# Qwiic_RFID_-_IDXXLA.net
KiCad netlist of a schematic drawn in EAGLE
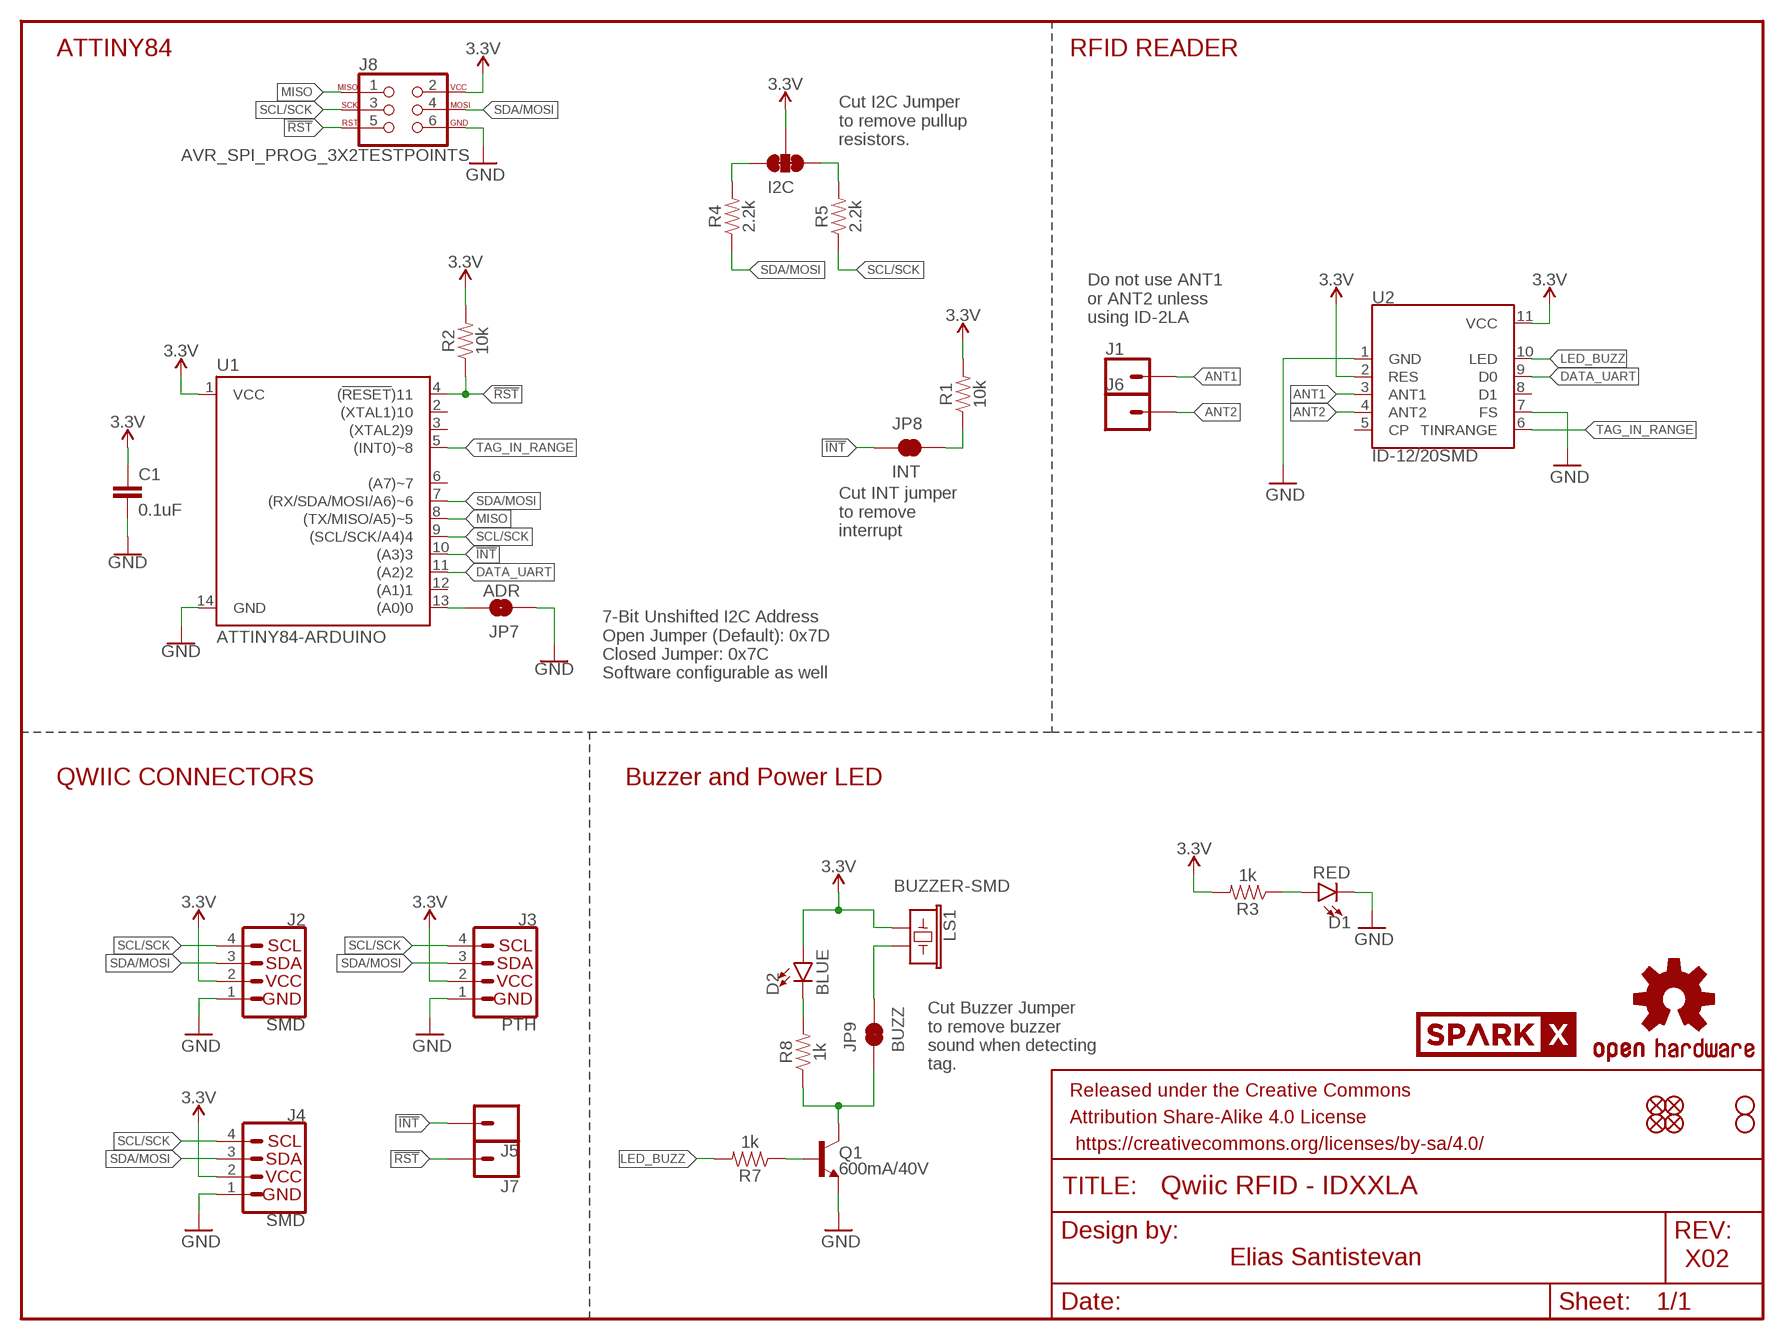
[diagram p0: schematic, sheet 1]

(export (version "E")
  (design (tool "Eeschema 10.0.6"))
  (components
    (comp (ref "C1")
      (value "0.1uF")
      (footprint "eagle-import:0603")
      (libsource (lib "eagle-import") (part "0.1UF-0603-25V-(+80/-20%)"))
    )
    (comp (ref "D1")
      (value "RED")
      (footprint "eagle-import:LED-0603")
      (libsource (lib "eagle-import") (part "LED-RED0603"))
    )
    (comp (ref "D2")
      (value "BLUE")
      (footprint "eagle-import:LED-0603")
      (libsource (lib "eagle-import") (part "LED-BLUE0603"))
    )
    (comp (ref "FRAME1")
      (value "FRAME-LETTER")
      (footprint "eagle-import:CREATIVE_COMMONS")
      (libsource (lib "eagle-import") (part "FRAME-LETTER"))
    )
    (comp (ref "I2C")
      (value "JUMPER-SMT_3_2-NC_TRACE_SILK")
      (footprint "eagle-import:SMT-JUMPER_3_2-NC_TRACE_SILK")
      (libsource (lib "eagle-import") (part "JUMPER-SMT_3_2-NC_TRACE_SILK"))
    )
    (comp (ref "J1")
      (value "CONN_01PTH_NO_SILK_YES_STOP")
      (footprint "eagle-import:1X01_NO_SILK")
      (libsource (lib "eagle-import") (part "CONN_01PTH_NO_SILK_YES_STOP"))
    )
    (comp (ref "J2")
      (value "SMD")
      (footprint "eagle-import:1X04_1MM_RA")
      (libsource (lib "eagle-import") (part "I2C_STANDARDJS-1MM"))
    )
    (comp (ref "J3")
      (value "PTH")
      (footprint "eagle-import:1X04_NO_SILK")
      (libsource (lib "eagle-import") (part "I2C_STANDARD_NO_SILK"))
    )
    (comp (ref "J4")
      (value "SMD")
      (footprint "eagle-import:1X04_1MM_RA")
      (libsource (lib "eagle-import") (part "I2C_STANDARDJS-1MM"))
    )
    (comp (ref "J5")
      (value "CONN_01PTH_NO_SILK_YES_STOP")
      (footprint "eagle-import:1X01_NO_SILK")
      (libsource (lib "eagle-import") (part "CONN_01PTH_NO_SILK_YES_STOP"))
    )
    (comp (ref "J6")
      (value "CONN_01PTH_NO_SILK_YES_STOP")
      (footprint "eagle-import:1X01_NO_SILK")
      (libsource (lib "eagle-import") (part "CONN_01PTH_NO_SILK_YES_STOP"))
    )
    (comp (ref "J7")
      (value "CONN_01PTH_NO_SILK_YES_STOP")
      (footprint "eagle-import:1X01_NO_SILK")
      (libsource (lib "eagle-import") (part "CONN_01PTH_NO_SILK_YES_STOP"))
    )
    (comp (ref "J8")
      (value "AVR_SPI_PROG_3X2TESTPOINTS")
      (footprint "eagle-import:2X3_TEST_POINTS")
      (libsource (lib "eagle-import") (part "AVR_SPI_PROG_3X2TESTPOINTS"))
    )
    (comp (ref "JP1")
      (value "FIDUCIALUFIDUCIAL")
      (footprint "eagle-import:MICRO-FIDUCIAL")
      (libsource (lib "eagle-import") (part "FIDUCIALUFIDUCIAL"))
    )
    (comp (ref "JP2")
      (value "FIDUCIALUFIDUCIAL")
      (footprint "eagle-import:MICRO-FIDUCIAL")
      (libsource (lib "eagle-import") (part "FIDUCIALUFIDUCIAL"))
    )
    (comp (ref "JP3")
      (value "STAND-OFF")
      (footprint "eagle-import:STAND-OFF")
      (libsource (lib "eagle-import") (part "STAND-OFF"))
    )
    (comp (ref "JP4")
      (value "STAND-OFF")
      (footprint "eagle-import:STAND-OFF")
      (libsource (lib "eagle-import") (part "STAND-OFF"))
    )
    (comp (ref "JP5")
      (value "FIDUCIALUFIDUCIAL")
      (footprint "eagle-import:MICRO-FIDUCIAL")
      (libsource (lib "eagle-import") (part "FIDUCIALUFIDUCIAL"))
    )
    (comp (ref "JP6")
      (value "FIDUCIALUFIDUCIAL")
      (footprint "eagle-import:MICRO-FIDUCIAL")
      (libsource (lib "eagle-import") (part "FIDUCIALUFIDUCIAL"))
    )
    (comp (ref "JP7")
      (value "ADR")
      (footprint "eagle-import:SMT-JUMPER_2_NO_SILK")
      (libsource (lib "eagle-import") (part "JUMPER-SMT_2_NO_SILK"))
    )
    (comp (ref "JP8")
      (value "INT")
      (footprint "eagle-import:SMT-JUMPER_2_NC_TRACE_SILK")
      (libsource (lib "eagle-import") (part "JUMPER-SMT_2_NC_TRACE_SILK"))
    )
    (comp (ref "JP9")
      (value "BUZZ")
      (footprint "eagle-import:SMT-JUMPER_2_NC_TRACE_SILK")
      (libsource (lib "eagle-import") (part "JUMPER-SMT_2_NC_TRACE_SILK"))
    )
    (comp (ref "LOGO1")
      (value "OSHW-LOGOMINI")
      (footprint "eagle-import:OSHW-LOGO-MINI")
      (libsource (lib "eagle-import") (part "OSHW-LOGOMINI"))
    )
    (comp (ref "LS1")
      (value "BUZZER-SMD")
      (footprint "eagle-import:BUZZER-CCV")
      (libsource (lib "eagle-import") (part "BUZZER-SMD"))
    )
    (comp (ref "Q1")
      (value "600mA/40V")
      (footprint "eagle-import:SOT23-3")
      (libsource (lib "eagle-import") (part "TRANS_NPN-MMBT2222AL"))
    )
    (comp (ref "R1")
      (value "10k")
      (footprint "eagle-import:0603")
      (libsource (lib "eagle-import") (part "10KOHM-0603-1/10W-1%"))
    )
    (comp (ref "R2")
      (value "10k")
      (footprint "eagle-import:0603")
      (libsource (lib "eagle-import") (part "10KOHM-0603-1/10W-1%"))
    )
    (comp (ref "R3")
      (value "1k")
      (footprint "eagle-import:0603")
      (libsource (lib "eagle-import") (part "1KOHM-0603-1/10W-1%"))
    )
    (comp (ref "R4")
      (value "2.2k")
      (footprint "eagle-import:0603")
      (libsource (lib "eagle-import") (part "2.2KOHM-0603-1/10W-1%"))
    )
    (comp (ref "R5")
      (value "2.2k")
      (footprint "eagle-import:0603")
      (libsource (lib "eagle-import") (part "2.2KOHM-0603-1/10W-1%"))
    )
    (comp (ref "R7")
      (value "1k")
      (footprint "eagle-import:0603")
      (libsource (lib "eagle-import") (part "1KOHM-0603-1/10W-1%"))
    )
    (comp (ref "R8")
      (value "1k")
      (footprint "eagle-import:0603")
      (libsource (lib "eagle-import") (part "1KOHM-0603-1/10W-1%"))
    )
    (comp (ref "U$4")
      (value "SPARKX-LOGO3")
      (footprint "eagle-import:SPARKX-SMALL")
      (libsource (lib "eagle-import") (part "SPARKX-LOGO3"))
    )
    (comp (ref "U1")
      (value "ATTINY84-ARDUINO")
      (footprint "eagle-import:SO14")
      (libsource (lib "eagle-import") (part "ATTINY84-ARDUINO"))
    )
    (comp (ref "U2")
      (value "ID-12/20SMD")
      (footprint "eagle-import:ID-12_SMD")
      (libsource (lib "eagle-import") (part "ID-12/20SMD"))
    )
  )
  (nets
    (net (code "1") (name "/~{INT}") (class "Default")
      (node (ref "J5") (pin "1") (pinfunction "1_1") (pintype "passive"))
      (node (ref "JP8") (pin "1") (pinfunction "1_1") (pintype "passive"))
      (node (ref "U1") (pin "10") (pinfunction "(A3)3_10") (pintype "bidirectional"))
    )
    (net (code "2") (name "/~{RST}") (class "Default")
      (node (ref "J7") (pin "1") (pinfunction "1_1") (pintype "passive"))
      (node (ref "J8") (pin "5") (pinfunction "5_5") (pintype "passive"))
      (node (ref "R2") (pin "1") (pinfunction "1_1") (pintype "passive"))
      (node (ref "U1") (pin "4") (pinfunction "(~{RESET})11_4") (pintype "bidirectional"))
    )
    (net (code "3") (name "3.3V") (class "Default")
      (node (ref "C1") (pin "1") (pinfunction "1_1") (pintype "passive"))
      (node (ref "D2") (pin "A") (pinfunction "A_A") (pintype "passive"))
      (node (ref "I2C") (pin "2") (pinfunction "2_2") (pintype "passive"))
      (node (ref "J2") (pin "2") (pinfunction "VCC_2") (pintype "power_in"))
      (node (ref "J3") (pin "2") (pinfunction "VCC_2") (pintype "power_in"))
      (node (ref "J4") (pin "2") (pinfunction "VCC_2") (pintype "power_in"))
      (node (ref "J8") (pin "2") (pinfunction "2_2") (pintype "passive"))
      (node (ref "LS1") (pin "+") (pinfunction "1_+") (pintype "passive"))
      (node (ref "R1") (pin "2") (pinfunction "2_2") (pintype "passive"))
      (node (ref "R2") (pin "2") (pinfunction "2_2") (pintype "passive"))
      (node (ref "R3") (pin "2") (pinfunction "2_2") (pintype "passive"))
      (node (ref "U1") (pin "1") (pinfunction "VCC_1") (pintype "bidirectional"))
      (node (ref "U2") (pin "11") (pinfunction "VCC_11") (pintype "bidirectional"))
      (node (ref "U2") (pin "2") (pinfunction "RES_2") (pintype "bidirectional"))
    )
    (net (code "4") (name "ANT1") (class "Default")
      (node (ref "J1") (pin "1") (pinfunction "1_1") (pintype "passive"))
      (node (ref "U2") (pin "3") (pinfunction "ANT1_3") (pintype "bidirectional"))
    )
    (net (code "5") (name "ANT2") (class "Default")
      (node (ref "J6") (pin "1") (pinfunction "1_1") (pintype "passive"))
      (node (ref "U2") (pin "4") (pinfunction "ANT2_4") (pintype "bidirectional"))
    )
    (net (code "6") (name "DATA_UART") (class "Default")
      (node (ref "U1") (pin "11") (pinfunction "(A2)2_11") (pintype "bidirectional"))
      (node (ref "U2") (pin "9") (pinfunction "D0_9") (pintype "bidirectional"))
    )
    (net (code "7") (name "GND") (class "Default")
      (node (ref "C1") (pin "2") (pinfunction "2_2") (pintype "passive"))
      (node (ref "D1") (pin "C") (pinfunction "C_C") (pintype "passive"))
      (node (ref "J2") (pin "1") (pinfunction "GND_1") (pintype "power_in"))
      (node (ref "J3") (pin "1") (pinfunction "GND_1") (pintype "power_in"))
      (node (ref "J4") (pin "1") (pinfunction "GND_1") (pintype "power_in"))
      (node (ref "J8") (pin "6") (pinfunction "6_6") (pintype "passive"))
      (node (ref "JP7") (pin "1") (pinfunction "1_1") (pintype "passive"))
      (node (ref "Q1") (pin "2") (pinfunction "E_2") (pintype "passive"))
      (node (ref "U1") (pin "14") (pinfunction "GND_14") (pintype "bidirectional"))
      (node (ref "U2") (pin "1") (pinfunction "GND_1") (pintype "bidirectional"))
      (node (ref "U2") (pin "7") (pinfunction "FS_7") (pintype "bidirectional"))
    )
    (net (code "8") (name "LED_BUZZ") (class "Default")
      (node (ref "R7") (pin "2") (pinfunction "2_2") (pintype "passive"))
      (node (ref "U2") (pin "10") (pinfunction "LED_10") (pintype "bidirectional"))
    )
    (net (code "9") (name "MISO") (class "Default")
      (node (ref "J8") (pin "1") (pinfunction "1_1") (pintype "passive"))
      (node (ref "U1") (pin "8") (pinfunction "(TX/MISO/A5)~{5}_8") (pintype "bidirectional"))
    )
    (net (code "10") (name "Net-(D1-PadA)") (class "Default")
      (node (ref "D1") (pin "A") (pinfunction "A_A") (pintype "passive"))
      (node (ref "R3") (pin "1") (pinfunction "1_1") (pintype "passive"))
    )
    (net (code "11") (name "Net-(D2-PadC)") (class "Default")
      (node (ref "D2") (pin "C") (pinfunction "C_C") (pintype "passive"))
      (node (ref "R8") (pin "2") (pinfunction "2_2") (pintype "passive"))
    )
    (net (code "12") (name "Net-(I2C-Pad1)") (class "Default")
      (node (ref "I2C") (pin "1") (pinfunction "1_1") (pintype "passive"))
      (node (ref "R5") (pin "2") (pinfunction "2_2") (pintype "passive"))
    )
    (net (code "13") (name "Net-(I2C-Pad3)") (class "Default")
      (node (ref "I2C") (pin "3") (pinfunction "3_3") (pintype "passive"))
      (node (ref "R4") (pin "2") (pinfunction "2_2") (pintype "passive"))
    )
    (net (code "14") (name "Net-(JP8-Pad2)") (class "Default")
      (node (ref "JP8") (pin "2") (pinfunction "2_2") (pintype "passive"))
      (node (ref "R1") (pin "1") (pinfunction "1_1") (pintype "passive"))
    )
    (net (code "15") (name "Net-(LS1-2)") (class "Default")
      (node (ref "JP9") (pin "2") (pinfunction "2_2") (pintype "passive"))
      (node (ref "LS1") (pin "-") (pinfunction "2_-") (pintype "passive"))
    )
    (net (code "16") (name "Net-(Q1-B)") (class "Default")
      (node (ref "Q1") (pin "1") (pinfunction "B_1") (pintype "passive"))
      (node (ref "R7") (pin "1") (pinfunction "1_1") (pintype "passive"))
    )
    (net (code "17") (name "Net-(Q1-C)") (class "Default")
      (node (ref "JP9") (pin "1") (pinfunction "1_1") (pintype "passive"))
      (node (ref "Q1") (pin "3") (pinfunction "C_3") (pintype "passive"))
      (node (ref "R8") (pin "1") (pinfunction "1_1") (pintype "passive"))
    )
    (net (code "18") (name "Net-(U1-(A0)0)") (class "Default")
      (node (ref "JP7") (pin "2") (pinfunction "2_2") (pintype "passive"))
      (node (ref "U1") (pin "13") (pinfunction "(A0)0_13") (pintype "bidirectional"))
    )
    (net (code "19") (name "SCL{slash}SCK") (class "Default")
      (node (ref "J2") (pin "4") (pinfunction "SCL_4") (pintype "passive"))
      (node (ref "J3") (pin "4") (pinfunction "SCL_4") (pintype "passive"))
      (node (ref "J4") (pin "4") (pinfunction "SCL_4") (pintype "passive"))
      (node (ref "J8") (pin "3") (pinfunction "3_3") (pintype "passive"))
      (node (ref "R5") (pin "1") (pinfunction "1_1") (pintype "passive"))
      (node (ref "U1") (pin "9") (pinfunction "(SCL/SCK/A4)4_9") (pintype "bidirectional"))
    )
    (net (code "20") (name "SDA{slash}MOSI") (class "Default")
      (node (ref "J2") (pin "3") (pinfunction "SDA_3") (pintype "passive"))
      (node (ref "J3") (pin "3") (pinfunction "SDA_3") (pintype "passive"))
      (node (ref "J4") (pin "3") (pinfunction "SDA_3") (pintype "passive"))
      (node (ref "J8") (pin "4") (pinfunction "4_4") (pintype "passive"))
      (node (ref "R4") (pin "1") (pinfunction "1_1") (pintype "passive"))
      (node (ref "U1") (pin "7") (pinfunction "(RX/SDA/MOSI/A6)~{6}_7") (pintype "bidirectional"))
    )
    (net (code "21") (name "TAG_IN_RANGE") (class "Default")
      (node (ref "U1") (pin "5") (pinfunction "(INT0)~{8}_5") (pintype "bidirectional"))
      (node (ref "U2") (pin "6") (pinfunction "TINRANGE_6") (pintype "bidirectional"))
    )
    (net (code "22") (name "unconnected-(U1-(A1)1-Pad12)") (class "Default")
      (node (ref "U1") (pin "12") (pinfunction "(A1)1_12") (pintype "bidirectional"))
    )
    (net (code "23") (name "unconnected-(U1-(A7)~{7}-Pad6)") (class "Default")
      (node (ref "U1") (pin "6") (pinfunction "(A7)~{7}_6") (pintype "bidirectional"))
    )
    (net (code "24") (name "unconnected-(U1-(XTAL1)10-Pad2)") (class "Default")
      (node (ref "U1") (pin "2") (pinfunction "(XTAL1)10_2") (pintype "bidirectional"))
    )
    (net (code "25") (name "unconnected-(U1-(XTAL2)9-Pad3)") (class "Default")
      (node (ref "U1") (pin "3") (pinfunction "(XTAL2)9_3") (pintype "bidirectional"))
    )
    (net (code "26") (name "unconnected-(U2-CP-Pad5)") (class "Default")
      (node (ref "U2") (pin "5") (pinfunction "CP_5") (pintype "bidirectional"))
    )
    (net (code "27") (name "unconnected-(U2-D1-Pad8)") (class "Default")
      (node (ref "U2") (pin "8") (pinfunction "D1_8") (pintype "bidirectional"))
    )
  )
)
